# teensyBoard_1_1.net
KiCad netlist of a schematic drawn in EAGLE
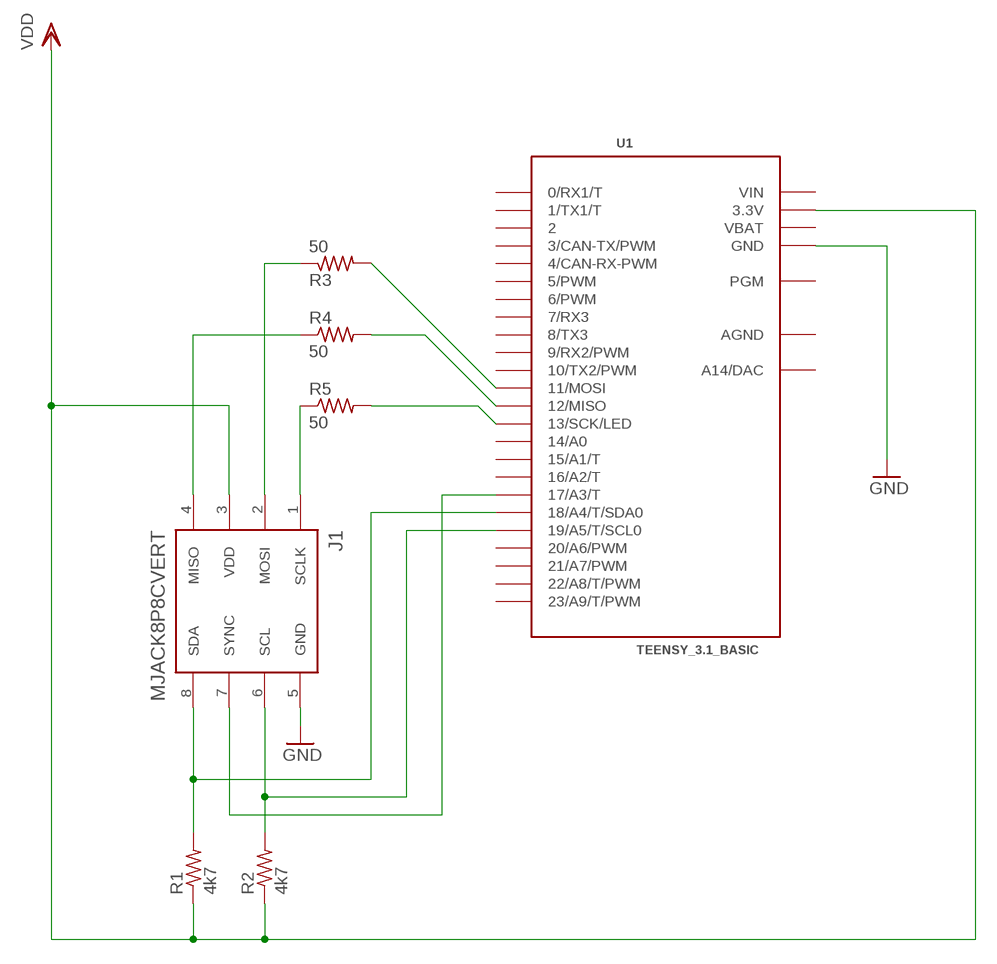
[diagram p0: schematic, sheet 1]

(export (version "E")
  (design (tool "Eeschema 10.0.6"))
  (components
    (comp (ref "J1")
      (value "MJACK8P8CVERT")
      (footprint "eagle-import:MJACK8P8C")
      (libsource (lib "eagle-import") (part "MJACK8P8CVERT"))
    )
    (comp (ref "R1")
      (value "4k7")
      (footprint "eagle-import:R0603")
      (libsource (lib "eagle-import") (part "R-US_R0603"))
    )
    (comp (ref "R2")
      (value "4k7")
      (footprint "eagle-import:R0603")
      (libsource (lib "eagle-import") (part "R-US_R0603"))
    )
    (comp (ref "R3")
      (value "50")
      (footprint "eagle-import:R0603")
      (libsource (lib "eagle-import") (part "R-US_R0603"))
    )
    (comp (ref "R4")
      (value "50")
      (footprint "eagle-import:R0603")
      (libsource (lib "eagle-import") (part "R-US_R0603"))
    )
    (comp (ref "R5")
      (value "50")
      (footprint "eagle-import:R0603")
      (libsource (lib "eagle-import") (part "R-US_R0603"))
    )
    (comp (ref "U1")
      (value "TEENSY_3.1_BASIC")
      (footprint "eagle-import:TEENSY_3.1_BASIC")
      (libsource (lib "eagle-import") (part "TEENSY_3.1_BASIC"))
    )
  )
  (nets
    (net (code "1") (name "/AGND") (class "Default")
      (node (ref "U1") (pin "AGND") (pinfunction "AGND_AGND") (pintype "power_in"))
    )
    (net (code "2") (name "/VBAT") (class "Default")
      (node (ref "U1") (pin "VBAT") (pinfunction "VBAT_VBAT") (pintype "power_in"))
    )
    (net (code "3") (name "/VIN") (class "Default")
      (node (ref "U1") (pin "VIN") (pinfunction "VIN_VIN") (pintype "power_in"))
    )
    (net (code "4") (name "GND") (class "Default")
      (node (ref "J1") (pin "5") (pinfunction "GND_5") (pintype "bidirectional"))
      (node (ref "U1") (pin "GND") (pinfunction "GND_GND") (pintype "power_in"))
      (node (ref "U1") (pin "GND1") (pinfunction "GND_GND1") (pintype "power_in"))
    )
    (net (code "5") (name "Net-(J1-MISO)") (class "Default")
      (node (ref "J1") (pin "4") (pinfunction "MISO_4") (pintype "bidirectional"))
      (node (ref "R4") (pin "1") (pinfunction "1_1") (pintype "passive"))
    )
    (net (code "6") (name "Net-(J1-MOSI)") (class "Default")
      (node (ref "J1") (pin "2") (pinfunction "MOSI_2") (pintype "bidirectional"))
      (node (ref "R3") (pin "1") (pinfunction "1_1") (pintype "passive"))
    )
    (net (code "7") (name "Net-(J1-SCL)") (class "Default")
      (node (ref "J1") (pin "6") (pinfunction "SCL_6") (pintype "bidirectional"))
      (node (ref "R2") (pin "2") (pinfunction "2_2") (pintype "passive"))
      (node (ref "U1") (pin "19/A5") (pinfunction "19/A5/T/SCL0_19/A5") (pintype "bidirectional"))
    )
    (net (code "8") (name "Net-(J1-SCLK)") (class "Default")
      (node (ref "J1") (pin "1") (pinfunction "SCLK_1") (pintype "bidirectional"))
      (node (ref "R5") (pin "1") (pinfunction "1_1") (pintype "passive"))
    )
    (net (code "9") (name "Net-(J1-SDA)") (class "Default")
      (node (ref "J1") (pin "8") (pinfunction "SDA_8") (pintype "bidirectional"))
      (node (ref "R1") (pin "2") (pinfunction "2_2") (pintype "passive"))
      (node (ref "U1") (pin "18/A4") (pinfunction "18/A4/T/SDA0_18/A4") (pintype "bidirectional"))
    )
    (net (code "10") (name "Net-(J1-SYNC)") (class "Default")
      (node (ref "J1") (pin "7") (pinfunction "SYNC_7") (pintype "bidirectional"))
      (node (ref "U1") (pin "17/A3") (pinfunction "17/A3/T_17/A3") (pintype "bidirectional"))
    )
    (net (code "11") (name "Net-(U1-11{slash}MOSI)") (class "Default")
      (node (ref "R3") (pin "2") (pinfunction "2_2") (pintype "passive"))
      (node (ref "U1") (pin "11") (pinfunction "11/MOSI_11") (pintype "bidirectional"))
    )
    (net (code "12") (name "Net-(U1-12{slash}MISO)") (class "Default")
      (node (ref "R4") (pin "2") (pinfunction "2_2") (pintype "passive"))
      (node (ref "U1") (pin "12") (pinfunction "12/MISO_12") (pintype "bidirectional"))
    )
    (net (code "13") (name "Net-(U1-13{slash}SCK{slash}LED)") (class "Default")
      (node (ref "R5") (pin "2") (pinfunction "2_2") (pintype "passive"))
      (node (ref "U1") (pin "13") (pinfunction "13/SCK/LED_13") (pintype "bidirectional"))
    )
    (net (code "14") (name "VDD") (class "Default")
      (node (ref "J1") (pin "3") (pinfunction "VDD_3") (pintype "bidirectional"))
      (node (ref "R1") (pin "1") (pinfunction "1_1") (pintype "passive"))
      (node (ref "R2") (pin "1") (pinfunction "1_1") (pintype "passive"))
      (node (ref "U1") (pin "3.3V") (pinfunction "3.3V_3.3V") (pintype "power_in"))
      (node (ref "U1") (pin "3.3V1") (pinfunction "3.3V_3.3V1") (pintype "power_in"))
    )
    (net (code "15") (name "unconnected-(U1-0{slash}RX1{slash}T-Pad0)") (class "Default")
      (node (ref "U1") (pin "0") (pinfunction "0/RX1/T_0") (pintype "bidirectional"))
    )
    (net (code "16") (name "unconnected-(U1-1{slash}TX1{slash}T-Pad1)") (class "Default")
      (node (ref "U1") (pin "1") (pinfunction "1/TX1/T_1") (pintype "bidirectional"))
    )
    (net (code "17") (name "unconnected-(U1-3{slash}CAN-TX{slash}PWM-Pad3)") (class "Default")
      (node (ref "U1") (pin "3") (pinfunction "3/CAN-TX/PWM_3") (pintype "bidirectional"))
    )
    (net (code "18") (name "unconnected-(U1-4{slash}CAN-RX-PWM-Pad4)") (class "Default")
      (node (ref "U1") (pin "4") (pinfunction "4/CAN-RX-PWM_4") (pintype "bidirectional"))
    )
    (net (code "19") (name "unconnected-(U1-5{slash}PWM-Pad5)") (class "Default")
      (node (ref "U1") (pin "5") (pinfunction "5/PWM_5") (pintype "bidirectional"))
    )
    (net (code "20") (name "unconnected-(U1-6{slash}PWM-Pad6)") (class "Default")
      (node (ref "U1") (pin "6") (pinfunction "6/PWM_6") (pintype "bidirectional"))
    )
    (net (code "21") (name "unconnected-(U1-7{slash}RX3-Pad7)") (class "Default")
      (node (ref "U1") (pin "7") (pinfunction "7/RX3_7") (pintype "bidirectional"))
    )
    (net (code "22") (name "unconnected-(U1-8{slash}TX3-Pad8)") (class "Default")
      (node (ref "U1") (pin "8") (pinfunction "8/TX3_8") (pintype "bidirectional"))
    )
    (net (code "23") (name "unconnected-(U1-9{slash}RX2{slash}PWM-Pad9)") (class "Default")
      (node (ref "U1") (pin "9") (pinfunction "9/RX2/PWM_9") (pintype "bidirectional"))
    )
    (net (code "24") (name "unconnected-(U1-10{slash}TX2{slash}PWM-Pad10)") (class "Default")
      (node (ref "U1") (pin "10") (pinfunction "10/TX2/PWM_10") (pintype "bidirectional"))
    )
    (net (code "25") (name "unconnected-(U1-15{slash}A1{slash}T-Pad15{slash}A1)") (class "Default")
      (node (ref "U1") (pin "15/A1") (pinfunction "15/A1/T_15/A1") (pintype "bidirectional"))
    )
    (net (code "26") (name "unconnected-(U1-16{slash}A2{slash}T-Pad16{slash}A2)") (class "Default")
      (node (ref "U1") (pin "16/A2") (pinfunction "16/A2/T_16/A2") (pintype "bidirectional"))
    )
    (net (code "27") (name "unconnected-(U1-20{slash}A6{slash}PWM-Pad20{slash}A6)") (class "Default")
      (node (ref "U1") (pin "20/A6") (pinfunction "20/A6/PWM_20/A6") (pintype "bidirectional"))
    )
    (net (code "28") (name "unconnected-(U1-21{slash}A7{slash}PWM-Pad21{slash}A7)") (class "Default")
      (node (ref "U1") (pin "21/A7") (pinfunction "21/A7/PWM_21/A7") (pintype "bidirectional"))
    )
    (net (code "29") (name "unconnected-(U1-22{slash}A8{slash}T{slash}PWM-Pad22{slash}A8)") (class "Default")
      (node (ref "U1") (pin "22/A8") (pinfunction "22/A8/T/PWM_22/A8") (pintype "bidirectional"))
    )
    (net (code "30") (name "unconnected-(U1-23{slash}A9{slash}T{slash}PWM-Pad23{slash}A9)") (class "Default")
      (node (ref "U1") (pin "23/A9") (pinfunction "23/A9/T/PWM_23/A9") (pintype "bidirectional"))
    )
    (net (code "31") (name "unconnected-(U1-A14{slash}DAC-PadA14)") (class "Default")
      (node (ref "U1") (pin "A14") (pinfunction "A14/DAC_A14") (pintype "bidirectional"))
    )
    (net (code "32") (name "unconnected-(U1-Pad2)") (class "Default")
      (node (ref "U1") (pin "2") (pinfunction "2_2") (pintype "bidirectional"))
    )
    (net (code "33") (name "unconnected-(U1-Pad14{slash}A0)") (class "Default")
      (node (ref "U1") (pin "14/A0") (pinfunction "14/A0_14/A0") (pintype "bidirectional"))
    )
    (net (code "34") (name "unconnected-(U1-PadPGM)") (class "Default")
      (node (ref "U1") (pin "PGM") (pinfunction "PGM_PGM") (pintype "bidirectional"))
    )
  )
)
